# Dual_Stepper_Control_Board.net
KiCad netlist of a schematic drawn in EAGLE
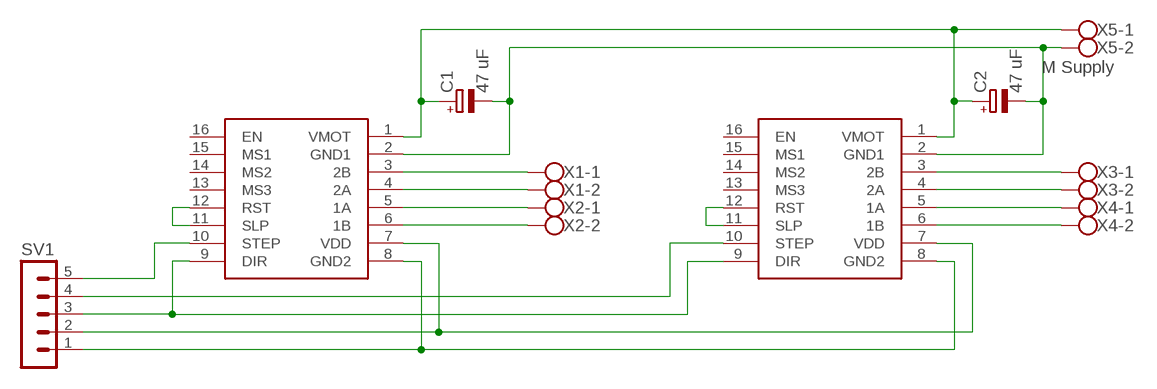
[diagram p0: schematic, sheet 1]

(export (version "E")
  (design (tool "Eeschema 10.0.6"))
  (components
    (comp (ref "C1")
      (value "47 uF")
      (footprint "eagle-import:E3,5-8")
      (libsource (lib "eagle-import") (part "CPOL-EUE3.5-8"))
    )
    (comp (ref "C2")
      (value "47 uF")
      (footprint "eagle-import:E3,5-8")
      (libsource (lib "eagle-import") (part "CPOL-EUE3.5-8"))
    )
    (comp (ref "SV1")
      (value "MA05-1")
      (footprint "eagle-import:MA05-1")
      (libsource (lib "eagle-import") (part "MA05-1"))
    )
    (comp (ref "U$1")
      (value "POLOLUESTEPPERDRIVER")
      (footprint "eagle-import:DIL16")
      (libsource (lib "eagle-import") (part "POLOLUESTEPPERDRIVER"))
    )
    (comp (ref "U$2")
      (value "POLOLUESTEPPERDRIVER")
      (footprint "eagle-import:DIL16")
      (libsource (lib "eagle-import") (part "POLOLUESTEPPERDRIVER"))
    )
    (comp (ref "X1")
      (value "W237-102")
      (footprint "eagle-import:W237-102")
      (fields (field (name "MPN") "237-102"))
      (libsource (lib "eagle-import") (part "W237-102"))
    )
    (comp (ref "X2")
      (value "W237-102")
      (footprint "eagle-import:W237-102")
      (fields (field (name "MPN") "237-102"))
      (libsource (lib "eagle-import") (part "W237-102"))
    )
    (comp (ref "X3")
      (value "W237-102")
      (footprint "eagle-import:W237-102")
      (fields (field (name "MPN") "237-102"))
      (libsource (lib "eagle-import") (part "W237-102"))
    )
    (comp (ref "X4")
      (value "W237-102")
      (footprint "eagle-import:W237-102")
      (fields (field (name "MPN") "237-102"))
      (libsource (lib "eagle-import") (part "W237-102"))
    )
    (comp (ref "X5")
      (value "M Supply")
      (footprint "eagle-import:W237-102")
      (fields (field (name "MPN") "237-102"))
      (libsource (lib "eagle-import") (part "W237-102"))
    )
  )
  (nets
    (net (code "1") (name "Net-(U$1-1A)") (class "Default")
      (node (ref "U$1") (pin "5") (pinfunction "1A_5") (pintype "output"))
      (node (ref "X2") (pin "1") (pinfunction "KL_1") (pintype "passive"))
    )
    (net (code "2") (name "Net-(U$1-1B)") (class "Default")
      (node (ref "U$1") (pin "6") (pinfunction "1B_6") (pintype "output"))
      (node (ref "X2") (pin "2") (pinfunction "KL_2") (pintype "passive"))
    )
    (net (code "3") (name "Net-(U$1-2A)") (class "Default")
      (node (ref "U$1") (pin "4") (pinfunction "2A_4") (pintype "output"))
      (node (ref "X1") (pin "2") (pinfunction "KL_2") (pintype "passive"))
    )
    (net (code "4") (name "Net-(U$1-2B)") (class "Default")
      (node (ref "U$1") (pin "3") (pinfunction "2B_3") (pintype "output"))
      (node (ref "X1") (pin "1") (pinfunction "KL_1") (pintype "passive"))
    )
    (net (code "5") (name "Net-(U$1-DIR)") (class "Default")
      (node (ref "SV1") (pin "3") (pinfunction "3_3") (pintype "passive"))
      (node (ref "U$1") (pin "9") (pinfunction "DIR_9") (pintype "input"))
      (node (ref "U$2") (pin "9") (pinfunction "DIR_9") (pintype "input"))
    )
    (net (code "6") (name "Net-(U$1-GND1)") (class "Default")
      (node (ref "C1") (pin "-") (pinfunction "-_-") (pintype "passive"))
      (node (ref "C2") (pin "-") (pinfunction "-_-") (pintype "passive"))
      (node (ref "U$1") (pin "2") (pinfunction "GND1_2") (pintype "power_in"))
      (node (ref "U$2") (pin "2") (pinfunction "GND1_2") (pintype "power_in"))
      (node (ref "X5") (pin "2") (pinfunction "KL_2") (pintype "passive"))
    )
    (net (code "7") (name "Net-(U$1-GND2)") (class "Default")
      (node (ref "SV1") (pin "1") (pinfunction "1_1") (pintype "passive"))
      (node (ref "U$1") (pin "8") (pinfunction "GND2_8") (pintype "power_in"))
      (node (ref "U$2") (pin "8") (pinfunction "GND2_8") (pintype "power_in"))
    )
    (net (code "8") (name "Net-(U$1-RST)") (class "Default")
      (node (ref "U$1") (pin "11") (pinfunction "SLP_11") (pintype "input"))
      (node (ref "U$1") (pin "12") (pinfunction "RST_12") (pintype "input"))
    )
    (net (code "9") (name "Net-(U$1-STEP)") (class "Default")
      (node (ref "SV1") (pin "5") (pinfunction "5_5") (pintype "passive"))
      (node (ref "U$1") (pin "10") (pinfunction "STEP_10") (pintype "input"))
    )
    (net (code "10") (name "Net-(U$1-VDD)") (class "Default")
      (node (ref "SV1") (pin "2") (pinfunction "2_2") (pintype "passive"))
      (node (ref "U$1") (pin "7") (pinfunction "VDD_7") (pintype "power_in"))
      (node (ref "U$2") (pin "7") (pinfunction "VDD_7") (pintype "power_in"))
    )
    (net (code "11") (name "Net-(U$1-VMOT)") (class "Default")
      (node (ref "C1") (pin "+") (pinfunction "+_+") (pintype "passive"))
      (node (ref "C2") (pin "+") (pinfunction "+_+") (pintype "passive"))
      (node (ref "U$1") (pin "1") (pinfunction "VMOT_1") (pintype "power_in"))
      (node (ref "U$2") (pin "1") (pinfunction "VMOT_1") (pintype "power_in"))
      (node (ref "X5") (pin "1") (pinfunction "KL_1") (pintype "passive"))
    )
    (net (code "12") (name "Net-(U$2-1A)") (class "Default")
      (node (ref "U$2") (pin "5") (pinfunction "1A_5") (pintype "output"))
      (node (ref "X4") (pin "1") (pinfunction "KL_1") (pintype "passive"))
    )
    (net (code "13") (name "Net-(U$2-1B)") (class "Default")
      (node (ref "U$2") (pin "6") (pinfunction "1B_6") (pintype "output"))
      (node (ref "X4") (pin "2") (pinfunction "KL_2") (pintype "passive"))
    )
    (net (code "14") (name "Net-(U$2-2A)") (class "Default")
      (node (ref "U$2") (pin "4") (pinfunction "2A_4") (pintype "output"))
      (node (ref "X3") (pin "2") (pinfunction "KL_2") (pintype "passive"))
    )
    (net (code "15") (name "Net-(U$2-2B)") (class "Default")
      (node (ref "U$2") (pin "3") (pinfunction "2B_3") (pintype "output"))
      (node (ref "X3") (pin "1") (pinfunction "KL_1") (pintype "passive"))
    )
    (net (code "16") (name "Net-(U$2-RST)") (class "Default")
      (node (ref "U$2") (pin "11") (pinfunction "SLP_11") (pintype "input"))
      (node (ref "U$2") (pin "12") (pinfunction "RST_12") (pintype "input"))
    )
    (net (code "17") (name "Net-(U$2-STEP)") (class "Default")
      (node (ref "SV1") (pin "4") (pinfunction "4_4") (pintype "passive"))
      (node (ref "U$2") (pin "10") (pinfunction "STEP_10") (pintype "input"))
    )
    (net (code "18") (name "unconnected-(U$1-EN-Pad16)") (class "Default")
      (node (ref "U$1") (pin "16") (pinfunction "EN_16") (pintype "input"))
    )
    (net (code "19") (name "unconnected-(U$1-MS1-Pad15)") (class "Default")
      (node (ref "U$1") (pin "15") (pinfunction "MS1_15") (pintype "input"))
    )
    (net (code "20") (name "unconnected-(U$1-MS2-Pad14)") (class "Default")
      (node (ref "U$1") (pin "14") (pinfunction "MS2_14") (pintype "input"))
    )
    (net (code "21") (name "unconnected-(U$1-MS3-Pad13)") (class "Default")
      (node (ref "U$1") (pin "13") (pinfunction "MS3_13") (pintype "input"))
    )
    (net (code "22") (name "unconnected-(U$2-EN-Pad16)") (class "Default")
      (node (ref "U$2") (pin "16") (pinfunction "EN_16") (pintype "input"))
    )
    (net (code "23") (name "unconnected-(U$2-MS1-Pad15)") (class "Default")
      (node (ref "U$2") (pin "15") (pinfunction "MS1_15") (pintype "input"))
    )
    (net (code "24") (name "unconnected-(U$2-MS2-Pad14)") (class "Default")
      (node (ref "U$2") (pin "14") (pinfunction "MS2_14") (pintype "input"))
    )
    (net (code "25") (name "unconnected-(U$2-MS3-Pad13)") (class "Default")
      (node (ref "U$2") (pin "13") (pinfunction "MS3_13") (pintype "input"))
    )
  )
)
